# Adafruit_LPS28_Pressure_Sensor.net
KiCad netlist of a schematic drawn in EAGLE
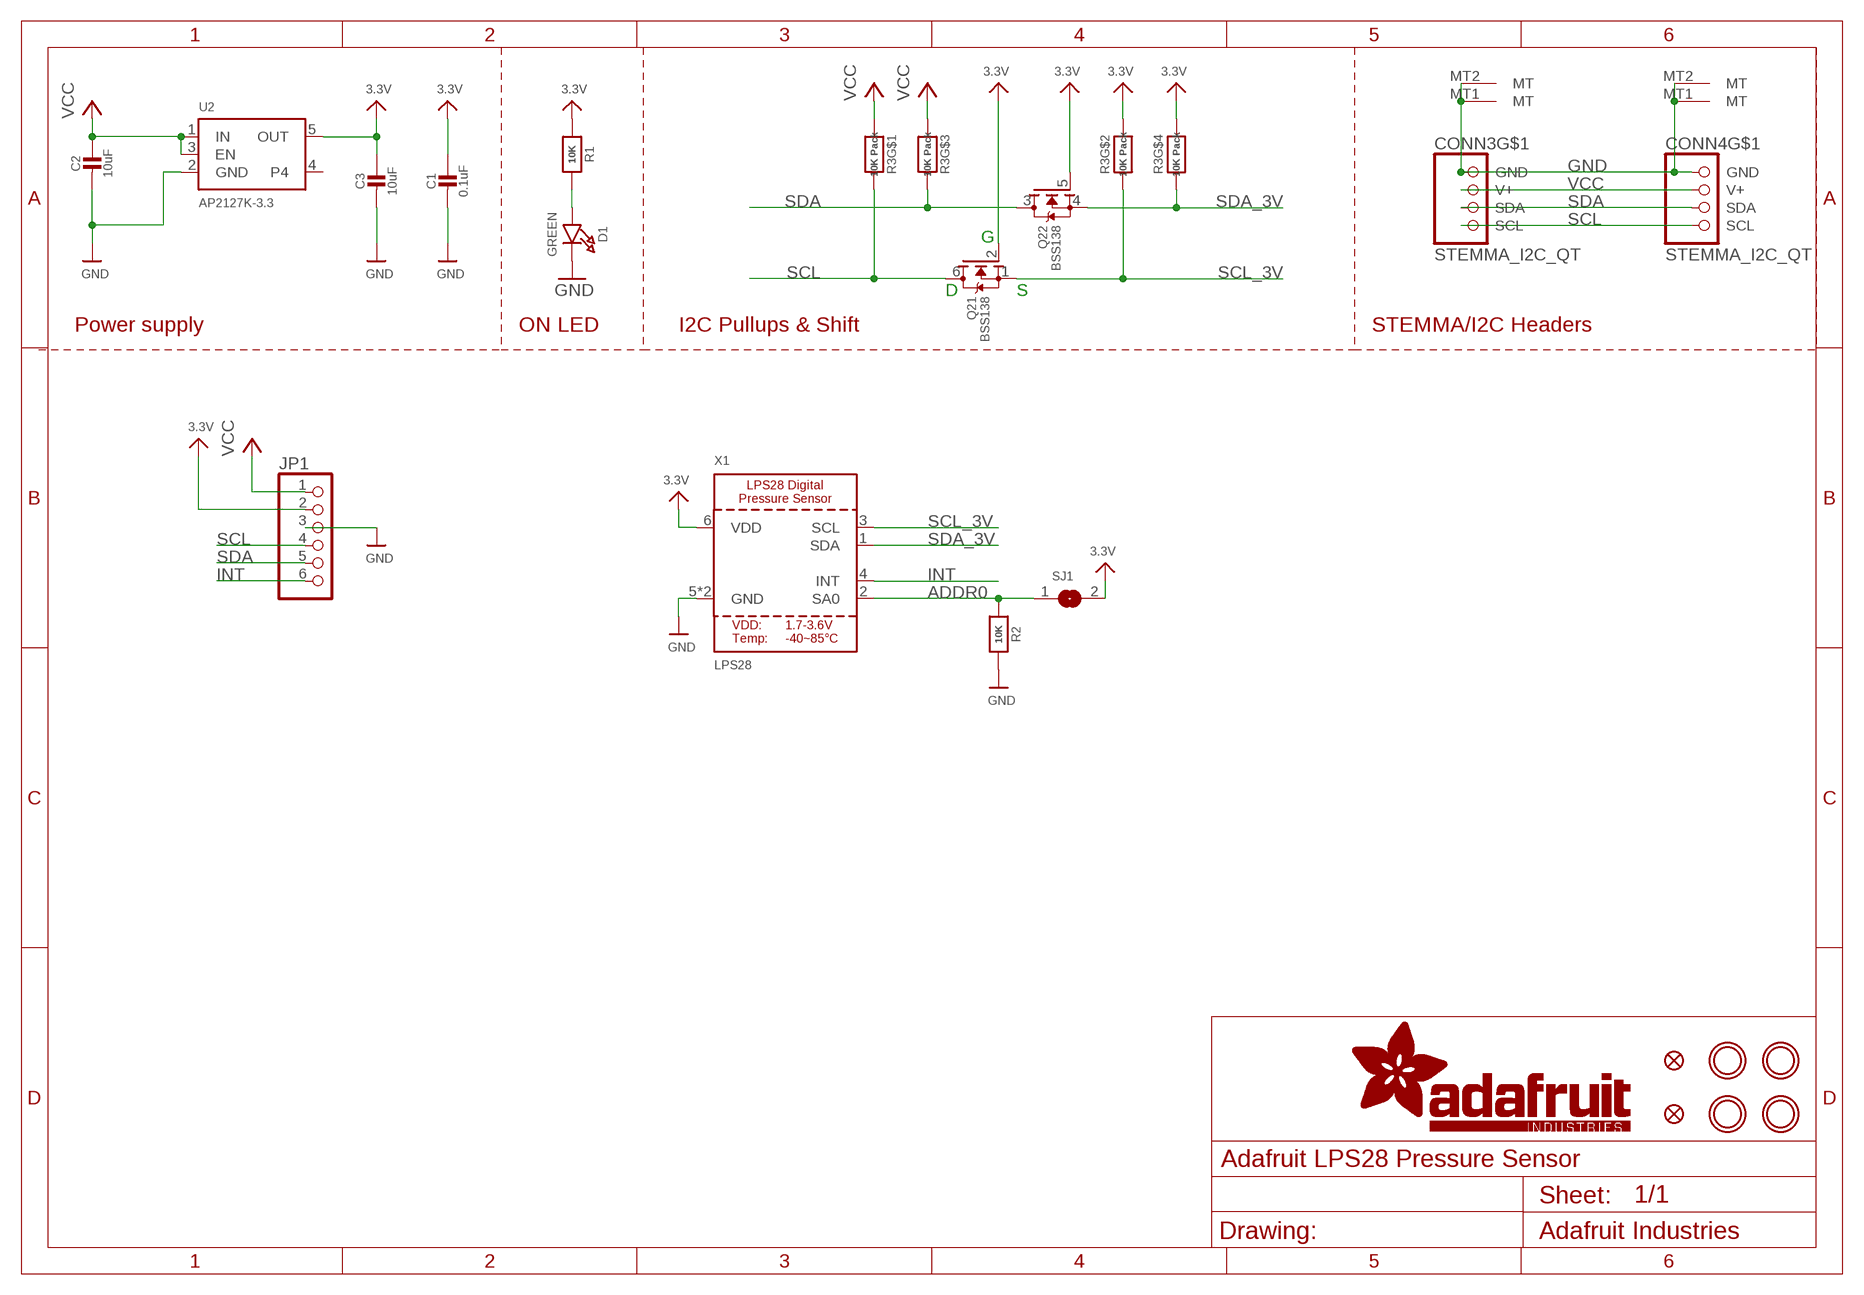
[diagram p0: schematic, sheet 1]

(export (version "E")
  (design (tool "Eeschema 10.0.6"))
  (components
    (comp (ref "C1")
      (value "0.1uF")
      (footprint "eagle-import:0603-NO")
      (libsource (lib "eagle-import") (part "CAP_CERAMIC0603_NO"))
    )
    (comp (ref "C2")
      (value "10uF")
      (footprint "eagle-import:0805-NO")
      (libsource (lib "eagle-import") (part "CAP_CERAMIC0805-NOOUTLINE"))
    )
    (comp (ref "C3")
      (value "10uF")
      (footprint "eagle-import:0805-NO")
      (libsource (lib "eagle-import") (part "CAP_CERAMIC0805-NOOUTLINE"))
    )
    (comp (ref "CONN3")
      (value "STEMMA_I2C_QT")
      (footprint "eagle-import:JST_SH4")
      (libsource (lib "eagle-import") (part "STEMMA_I2C_QT"))
    )
    (comp (ref "CONN4")
      (value "STEMMA_I2C_QT")
      (footprint "eagle-import:JST_SH4")
      (libsource (lib "eagle-import") (part "STEMMA_I2C_QT"))
    )
    (comp (ref "D1")
      (value "GREEN")
      (footprint "eagle-import:CHIPLED_0603_NOOUTLINE")
      (libsource (lib "eagle-import") (part "LED0603_NOOUTLINE"))
    )
    (comp (ref "FID3")
      (value "FIDUCIAL_1MM")
      (footprint "eagle-import:FIDUCIAL_1MM")
      (libsource (lib "eagle-import") (part "FIDUCIAL_1MM"))
    )
    (comp (ref "FID4")
      (value "FIDUCIAL_1MM")
      (footprint "eagle-import:FIDUCIAL_1MM")
      (libsource (lib "eagle-import") (part "FIDUCIAL_1MM"))
    )
    (comp (ref "JP1")
      (value "HEADER-1X670MIL")
      (footprint "eagle-import:1X06_ROUND_70")
      (libsource (lib "eagle-import") (part "HEADER-1X670MIL"))
    )
    (comp (ref "Q2")
      (value "BSS138")
      (footprint "eagle-import:SOT363")
      (libsource (lib "eagle-import") (part "MOSFET-N_DUAL"))
    )
    (comp (ref "R1")
      (value "10K")
      (footprint "eagle-import:0603-NO")
      (libsource (lib "eagle-import") (part "RESISTOR_0603_NOOUT"))
    )
    (comp (ref "R2")
      (value "10K")
      (footprint "eagle-import:0603-NO")
      (libsource (lib "eagle-import") (part "RESISTOR_0603_NOOUT"))
    )
    (comp (ref "R3")
      (value "10K Pack")
      (footprint "eagle-import:RESPACK_4X0603")
      (libsource (lib "eagle-import") (part "RESISTOR_4PACK"))
    )
    (comp (ref "SJ1")
      (value "SOLDERJUMPER")
      (footprint "eagle-import:SOLDERJUMPER_ARROW_NOPASTE")
      (libsource (lib "eagle-import") (part "SOLDERJUMPER"))
    )
    (comp (ref "U$1")
      (value "MOUNTINGHOLE2.5")
      (footprint "eagle-import:MOUNTINGHOLE_2.5_PLATED")
      (libsource (lib "eagle-import") (part "MOUNTINGHOLE2.5"))
    )
    (comp (ref "U$17")
      (value "MOUNTINGHOLE2.5")
      (footprint "eagle-import:MOUNTINGHOLE_2.5_PLATED")
      (libsource (lib "eagle-import") (part "MOUNTINGHOLE2.5"))
    )
    (comp (ref "U$19")
      (value "MOUNTINGHOLE2.5")
      (footprint "eagle-import:MOUNTINGHOLE_2.5_PLATED")
      (libsource (lib "eagle-import") (part "MOUNTINGHOLE2.5"))
    )
    (comp (ref "U$21")
      (value "MOUNTINGHOLE2.5")
      (footprint "eagle-import:MOUNTINGHOLE_2.5_PLATED")
      (libsource (lib "eagle-import") (part "MOUNTINGHOLE2.5"))
    )
    (comp (ref "U2")
      (value "AP2127K-3.3")
      (footprint "eagle-import:SOT23-5")
      (libsource (lib "eagle-import") (part "VREG_SOT23-5"))
    )
    (comp (ref "X1")
      (value "LPS28")
      (footprint "eagle-import:LPS28")
      (libsource (lib "eagle-import") (part "LPS28"))
    )
  )
  (nets
    (net (code "1") (name "/ADDR0") (class "Default")
      (node (ref "R2") (pin "1") (pinfunction "1_1") (pintype "passive"))
      (node (ref "SJ1") (pin "1") (pinfunction "1_1") (pintype "passive"))
      (node (ref "X1") (pin "2") (pinfunction "SA0_2") (pintype "input"))
    )
    (net (code "2") (name "/INT") (class "Default")
      (node (ref "JP1") (pin "6") (pinfunction "6_6") (pintype "passive"))
      (node (ref "X1") (pin "4") (pinfunction "INT_4") (pintype "output"))
    )
    (net (code "3") (name "/SCL") (class "Default")
      (node (ref "CONN3") (pin "4") (pinfunction "SCL_4") (pintype "passive"))
      (node (ref "CONN4") (pin "4") (pinfunction "SCL_4") (pintype "passive"))
      (node (ref "JP1") (pin "4") (pinfunction "4_4") (pintype "passive"))
      (node (ref "Q2") (pin "6") (pinfunction "D_6") (pintype "bidirectional"))
      (node (ref "R3") (pin "8") (pinfunction "2_8") (pintype "passive"))
    )
    (net (code "4") (name "/SCL_3V") (class "Default")
      (node (ref "Q2") (pin "1") (pinfunction "S_1") (pintype "bidirectional"))
      (node (ref "R3") (pin "7") (pinfunction "2_7") (pintype "passive"))
      (node (ref "X1") (pin "3") (pinfunction "SCL_3") (pintype "input"))
    )
    (net (code "5") (name "/SDA") (class "Default")
      (node (ref "CONN3") (pin "3") (pinfunction "SDA_3") (pintype "passive"))
      (node (ref "CONN4") (pin "3") (pinfunction "SDA_3") (pintype "passive"))
      (node (ref "JP1") (pin "5") (pinfunction "5_5") (pintype "passive"))
      (node (ref "Q2") (pin "3") (pinfunction "D_3") (pintype "bidirectional"))
      (node (ref "R3") (pin "6") (pinfunction "2_6") (pintype "passive"))
    )
    (net (code "6") (name "/SDA_3V") (class "Default")
      (node (ref "Q2") (pin "4") (pinfunction "S_4") (pintype "bidirectional"))
      (node (ref "R3") (pin "5") (pinfunction "2_5") (pintype "passive"))
      (node (ref "X1") (pin "1") (pinfunction "SDA_1") (pintype "bidirectional"))
    )
    (net (code "7") (name "3.3V") (class "Default")
      (node (ref "C1") (pin "1") (pinfunction "1_1") (pintype "passive"))
      (node (ref "C3") (pin "1") (pinfunction "1_1") (pintype "passive"))
      (node (ref "JP1") (pin "2") (pinfunction "2_2") (pintype "passive"))
      (node (ref "Q2") (pin "2") (pinfunction "G_2") (pintype "bidirectional"))
      (node (ref "Q2") (pin "5") (pinfunction "G_5") (pintype "bidirectional"))
      (node (ref "R1") (pin "1") (pinfunction "1_1") (pintype "passive"))
      (node (ref "R3") (pin "2") (pinfunction "1_2") (pintype "passive"))
      (node (ref "R3") (pin "4") (pinfunction "1_4") (pintype "passive"))
      (node (ref "SJ1") (pin "2") (pinfunction "2_2") (pintype "passive"))
      (node (ref "U2") (pin "5") (pinfunction "OUT_5") (pintype "power_in"))
      (node (ref "X1") (pin "6") (pinfunction "VDD_6") (pintype "power_in"))
    )
    (net (code "8") (name "GND") (class "Default")
      (node (ref "C1") (pin "2") (pinfunction "2_2") (pintype "passive"))
      (node (ref "C2") (pin "2") (pinfunction "2_2") (pintype "passive"))
      (node (ref "C3") (pin "2") (pinfunction "2_2") (pintype "passive"))
      (node (ref "CONN3") (pin "1") (pinfunction "GND_1") (pintype "passive"))
      (node (ref "CONN3") (pin "MT1") (pinfunction "MT_MT1") (pintype "bidirectional"))
      (node (ref "CONN3") (pin "MT2") (pinfunction "MT_MT2") (pintype "bidirectional"))
      (node (ref "CONN4") (pin "1") (pinfunction "GND_1") (pintype "passive"))
      (node (ref "CONN4") (pin "MT1") (pinfunction "MT_MT1") (pintype "bidirectional"))
      (node (ref "CONN4") (pin "MT2") (pinfunction "MT_MT2") (pintype "bidirectional"))
      (node (ref "D1") (pin "C") (pinfunction "C_C") (pintype "passive"))
      (node (ref "JP1") (pin "3") (pinfunction "3_3") (pintype "passive"))
      (node (ref "R2") (pin "2") (pinfunction "2_2") (pintype "passive"))
      (node (ref "U2") (pin "2") (pinfunction "GND_2") (pintype "power_in"))
      (node (ref "X1") (pin "5") (pinfunction "GND_5") (pintype "power_in"))
      (node (ref "X1") (pin "7") (pinfunction "GND_7") (pintype "power_in"))
    )
    (net (code "9") (name "Net-(D1-PadA)") (class "Default")
      (node (ref "D1") (pin "A") (pinfunction "A_A") (pintype "passive"))
      (node (ref "R1") (pin "2") (pinfunction "2_2") (pintype "passive"))
    )
    (net (code "10") (name "VCC") (class "Default")
      (node (ref "C2") (pin "1") (pinfunction "1_1") (pintype "passive"))
      (node (ref "CONN3") (pin "2") (pinfunction "V+_2") (pintype "passive"))
      (node (ref "CONN4") (pin "2") (pinfunction "V+_2") (pintype "passive"))
      (node (ref "JP1") (pin "1") (pinfunction "1_1") (pintype "passive"))
      (node (ref "R3") (pin "1") (pinfunction "1_1") (pintype "passive"))
      (node (ref "R3") (pin "3") (pinfunction "1_3") (pintype "passive"))
      (node (ref "U2") (pin "1") (pinfunction "IN_1") (pintype "power_in"))
      (node (ref "U2") (pin "3") (pinfunction "EN_3") (pintype "input"))
    )
    (net (code "11") (name "unconnected-(U2-P4-Pad4)") (class "Default")
      (node (ref "U2") (pin "4") (pinfunction "P4_4") (pintype "bidirectional"))
    )
  )
)
